# Transformer.net
KiCad netlist of a schematic drawn in Altium Designer
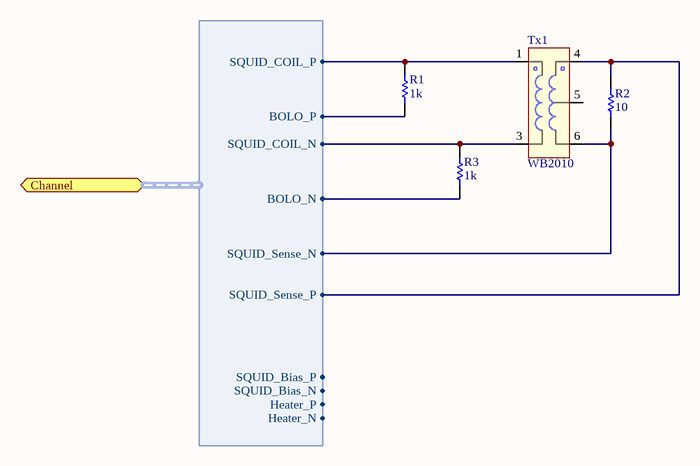
[diagram p0: Transformer.SchDoc]

(export (version "E")
  (design (tool "Eeschema 10.0.6"))
  (components
    (comp (ref "R1")
      (value "1k")
      (footprint "0603")
      (description "Resistor")
      (fields (field (name "TOLERANCE") "1%") (field (name "POWER") "1/10W"))
      (libsource (lib "MGNGSQ4_Dongles") (part "RES 0603"))
    )
    (comp (ref "R2")
      (value "10")
      (footprint "0603")
      (description "Resistor")
      (fields (field (name "TOLERANCE") "1%") (field (name "POWER") "1/10W"))
      (libsource (lib "MGNGSQ4_Dongles") (part "RES 0603"))
    )
    (comp (ref "R3")
      (value "1k")
      (footprint "0603")
      (description "Resistor")
      (fields (field (name "TOLERANCE") "1%") (field (name "POWER") "1/10W"))
      (libsource (lib "MGNGSQ4_Dongles") (part "RES 0603"))
    )
    (comp (ref "Tx1")
      (value "WB2010")
      (footprint "WB2010")
      (description "WB2010 1:1 Transformer")
      (libsource (lib "MGNGSQ4_Dongles") (part "WB2010"))
    )
  )
  (nets
    (net (code "2") (name "/BOLO_N") (class "Default")
      (node (ref "R3") (pin "1") (pinfunction "1_1") (pintype "passive"))
    )
    (net (code "3") (name "/BOLO_P") (class "Default")
      (node (ref "R1") (pin "1") (pinfunction "1_1") (pintype "passive"))
    )
    (net (code "4") (name "/SQUID_COIL_N") (class "Default")
      (node (ref "R3") (pin "2") (pinfunction "2_2") (pintype "passive"))
      (node (ref "Tx1") (pin "3") (pinfunction "3_3") (pintype "passive"))
    )
    (net (code "5") (name "/SQUID_COIL_P") (class "Default")
      (node (ref "R1") (pin "2") (pinfunction "2_2") (pintype "passive"))
      (node (ref "Tx1") (pin "1") (pinfunction "1_1") (pintype "passive"))
    )
    (net (code "6") (name "/SQUID_Sense_N") (class "Default")
      (node (ref "R2") (pin "1") (pinfunction "1_1") (pintype "passive"))
      (node (ref "Tx1") (pin "6") (pinfunction "6_6") (pintype "passive"))
    )
    (net (code "7") (name "/SQUID_Sense_P") (class "Default")
      (node (ref "R2") (pin "2") (pinfunction "2_2") (pintype "passive"))
      (node (ref "Tx1") (pin "4") (pinfunction "4_4") (pintype "passive"))
    )
    (net (code "9") (name "unconnected-(Tx1-Pad5)") (class "Default")
      (node (ref "Tx1") (pin "5") (pinfunction "5_5") (pintype "passive"))
    )
  )
)
